# Main.net
KiCad netlist of a schematic drawn in Altium Designer
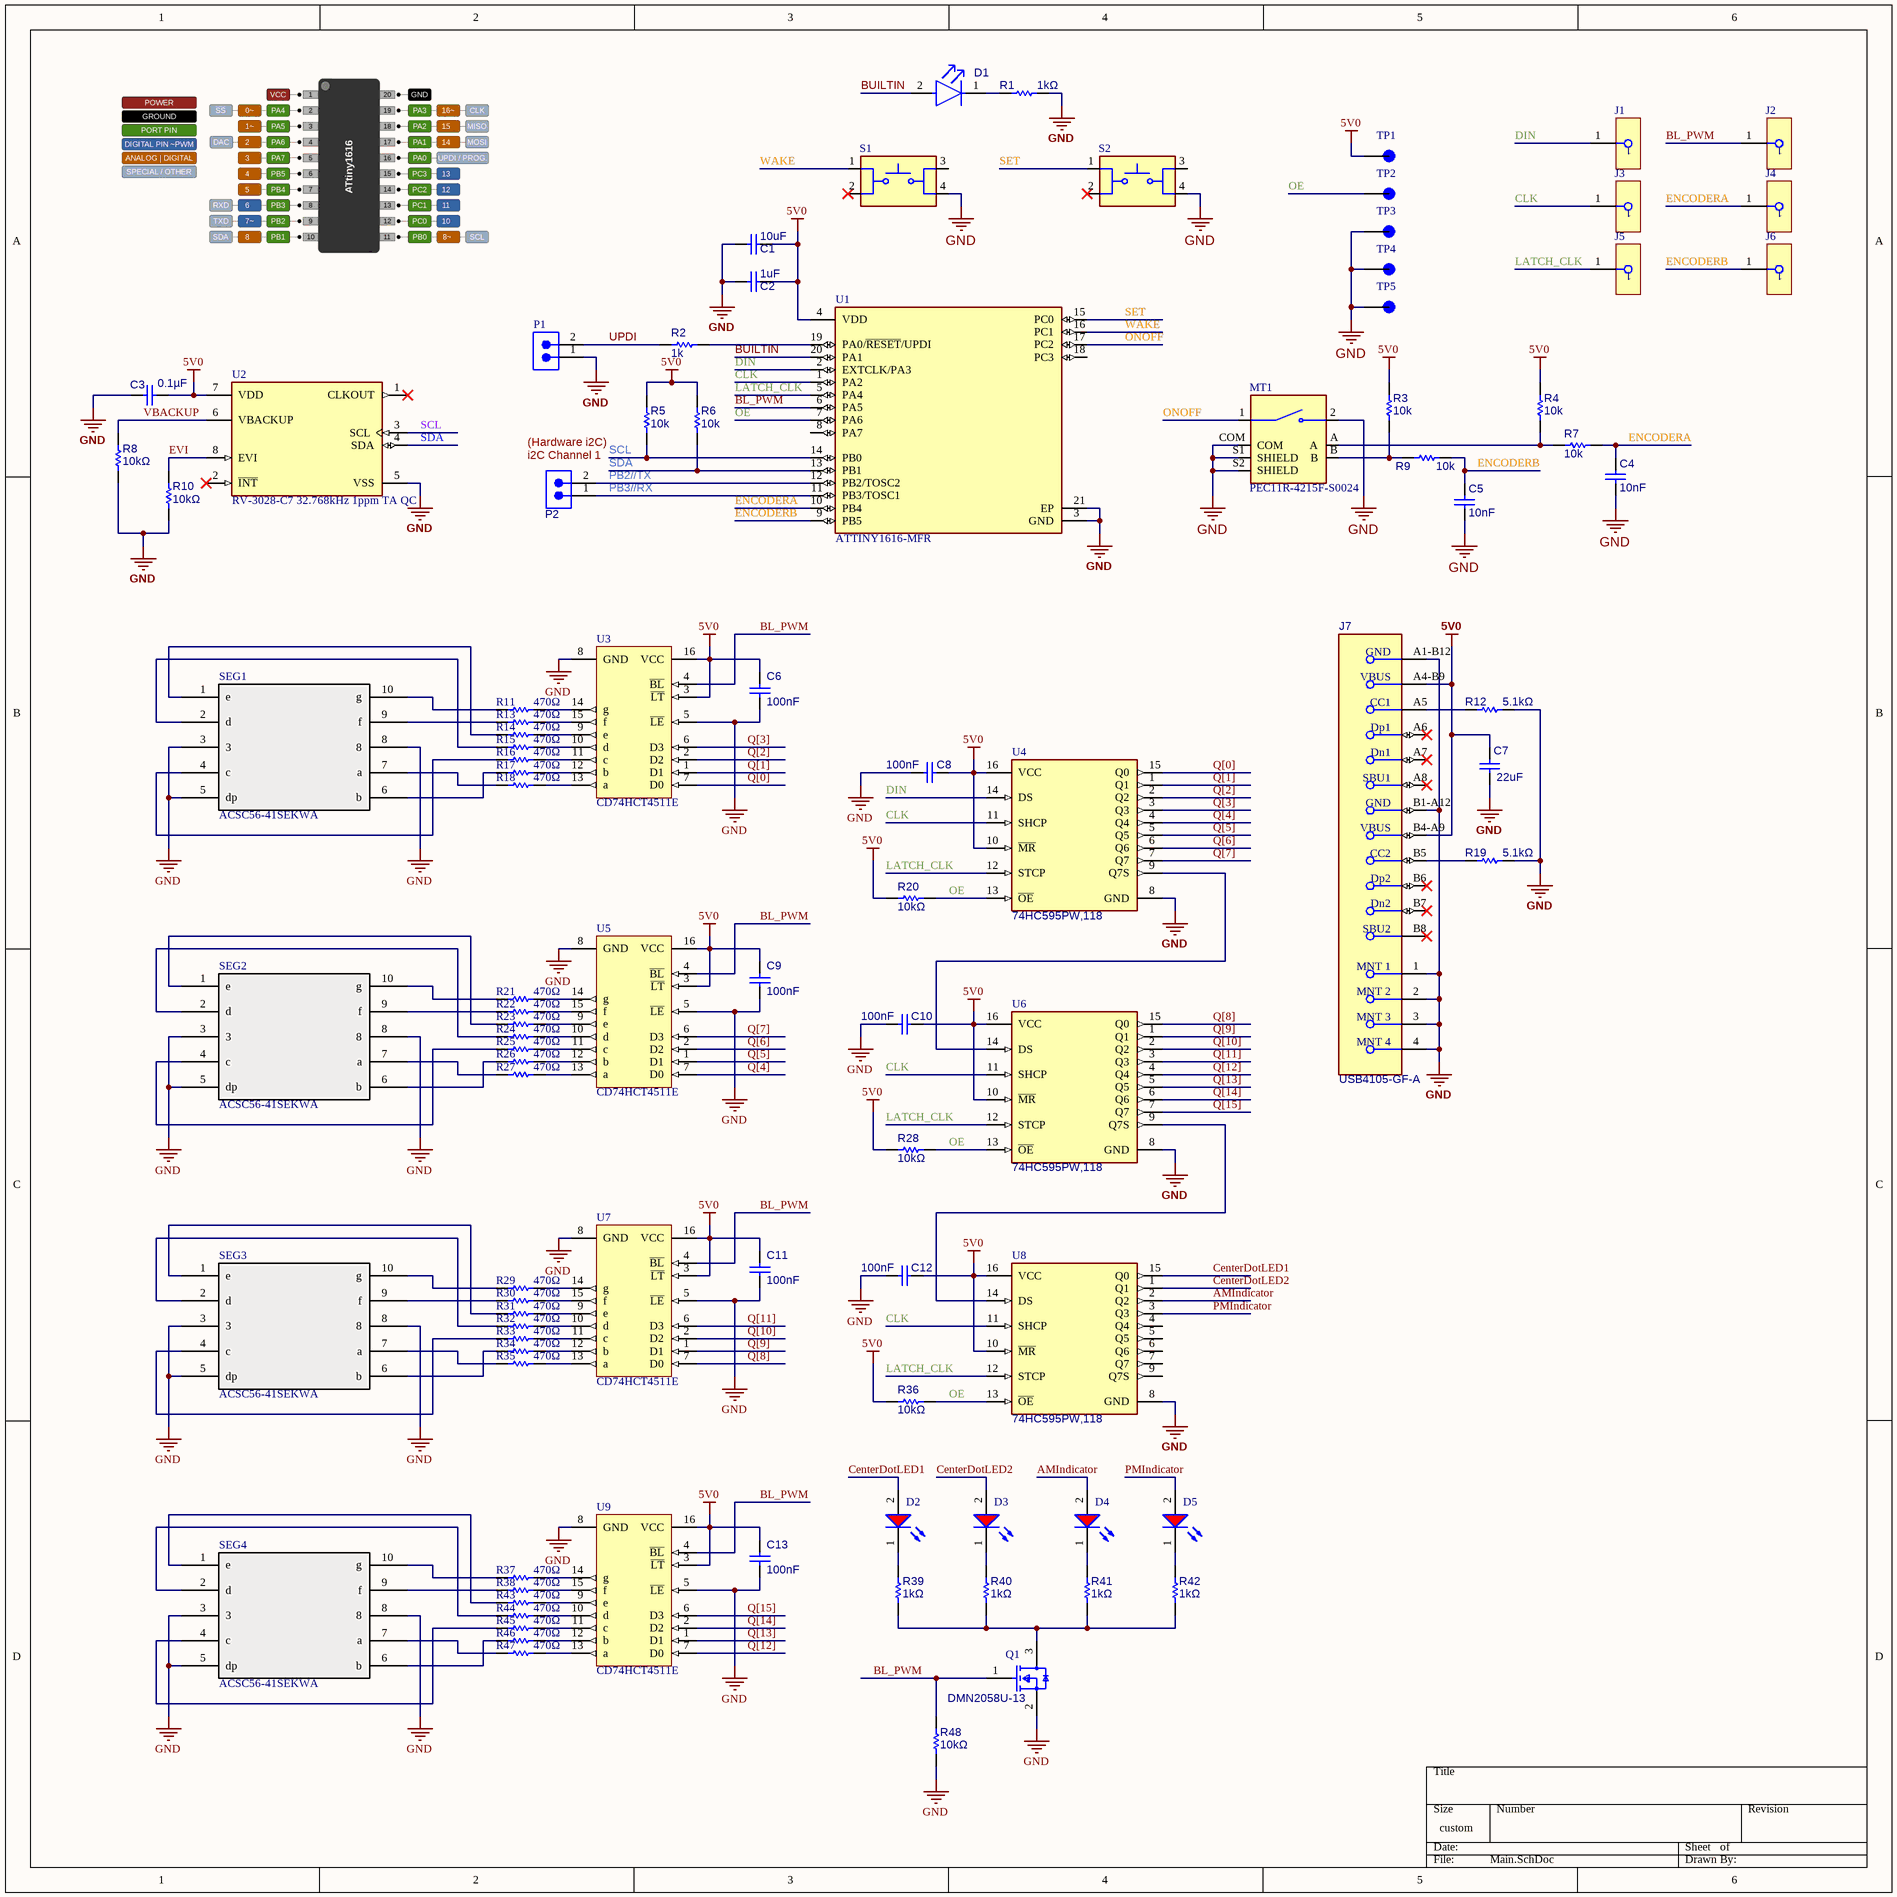
[diagram p0: Main.SchDoc]

(export (version "E")
  (design (tool "Eeschema 10.0.6"))
  (components
    (comp (ref "C1")
      (value "10uF")
      (footprint "WCAP-CSGP_0603_L1.6W0.8H0.8_Reflow")
      (description "10V tolerance")
      (libsource (lib "Altium Content Vault") (part "Capacitor_Non-Polarized"))
    )
    (comp (ref "C2")
      (value "1uF")
      (footprint "WCAP-CSGP_0603_L1.6W0.8H0.8_Reflow")
      (description "10V tolerance")
      (libsource (lib "Altium Content Vault") (part "Capacitor_Non-Polarized"))
    )
    (comp (ref "C3")
      (value "0.1µF")
      (footprint "WCAP-CSGP_0603_L1.6W0.8H0.8_Reflow")
      (description "10V tolerance")
      (libsource (lib "Altium Content Vault") (part "Capacitor_Non-Polarized"))
    )
    (comp (ref "C4")
      (value "10nF")
      (footprint "WCAP-CSGP_0603_L1.6W0.8H0.8_Reflow")
      (description "10V tolerance")
      (libsource (lib "Altium Content Vault") (part "Capacitor_Non-Polarized"))
    )
    (comp (ref "C5")
      (value "10nF")
      (footprint "WCAP-CSGP_0603_L1.6W0.8H0.8_Reflow")
      (description "10V tolerance")
      (libsource (lib "Altium Content Vault") (part "Capacitor_Non-Polarized"))
    )
    (comp (ref "C6")
      (value "100nF")
      (footprint "WCAP-CSGP_0603_L1.6W0.8H0.8_Reflow")
      (description "10V tolerance")
      (libsource (lib "Altium Content Vault") (part "Capacitor_Non-Polarized"))
    )
    (comp (ref "C7")
      (value "22uF")
      (footprint "WCAP-CSGP_0603_L1.6W0.8H0.8_Reflow")
      (description "10V tolerance")
      (libsource (lib "Altium Content Vault") (part "Capacitor_Non-Polarized"))
    )
    (comp (ref "C8")
      (value "100nF")
      (footprint "WCAP-CSGP_0603_L1.6W0.8H0.8_Reflow")
      (description "10V tolerance")
      (libsource (lib "Altium Content Vault") (part "Capacitor_Non-Polarized"))
    )
    (comp (ref "C9")
      (value "100nF")
      (footprint "WCAP-CSGP_0603_L1.6W0.8H0.8_Reflow")
      (description "10V tolerance")
      (libsource (lib "Altium Content Vault") (part "Capacitor_Non-Polarized"))
    )
    (comp (ref "C10")
      (value "100nF")
      (footprint "WCAP-CSGP_0603_L1.6W0.8H0.8_Reflow")
      (description "10V tolerance")
      (libsource (lib "Altium Content Vault") (part "Capacitor_Non-Polarized"))
    )
    (comp (ref "C11")
      (value "100nF")
      (footprint "WCAP-CSGP_0603_L1.6W0.8H0.8_Reflow")
      (description "10V tolerance")
      (libsource (lib "Altium Content Vault") (part "Capacitor_Non-Polarized"))
    )
    (comp (ref "C12")
      (value "100nF")
      (footprint "WCAP-CSGP_0603_L1.6W0.8H0.8_Reflow")
      (description "10V tolerance")
      (libsource (lib "Altium Content Vault") (part "Capacitor_Non-Polarized"))
    )
    (comp (ref "C13")
      (value "100nF")
      (footprint "WCAP-CSGP_0603_L1.6W0.8H0.8_Reflow")
      (description "10V tolerance")
      (libsource (lib "Altium Content Vault") (part "Capacitor_Non-Polarized"))
    )
    (comp (ref "D1")
      (value "LTST-C190KGKT")
      (footprint "FP-LTST-C190KGKT-MFG")
      (description "LED GREEN CLEAR CHIP SMD")
      (libsource (lib "Altium Content Vault") (part "8706943c75ba83719d021d2fdc84c58"))
    )
    (comp (ref "D2")
      (value "150120RS75000")
      (footprint "WL-SMCW_1206_150120xx75000")
      (description "WL-SMCW SMT Mono-Color Chip LED Waterclear")
      (libsource (lib "Altium Content Vault") (part "LED_Red_2A-1K"))
    )
    (comp (ref "D3")
      (value "150120RS75000")
      (footprint "WL-SMCW_1206_150120xx75000")
      (description "WL-SMCW SMT Mono-Color Chip LED Waterclear")
      (libsource (lib "Altium Content Vault") (part "LED_Red_2A-1K"))
    )
    (comp (ref "D4")
      (value "150120RS75000")
      (footprint "WL-SMCW_1206_150120xx75000")
      (description "WL-SMCW SMT Mono-Color Chip LED Waterclear")
      (libsource (lib "Altium Content Vault") (part "LED_Red_2A-1K"))
    )
    (comp (ref "D5")
      (value "150120RS75000")
      (footprint "WL-SMCW_1206_150120xx75000")
      (description "WL-SMCW SMT Mono-Color Chip LED Waterclear")
      (libsource (lib "Altium Content Vault") (part "LED_Red_2A-1K"))
    )
    (comp (ref "J1")
      (value "5019")
      (footprint "5019_MFG")
      (description "Phosphor Bronze Contact Miniature Silver Plated Surface Mount Test Points")
      (libsource (lib "Altium Content Vault") (part "2b5a64f1d553f7b761d27cd6d0c3a70"))
    )
    (comp (ref "J2")
      (value "5019")
      (footprint "5019_MFG")
      (description "Phosphor Bronze Contact Miniature Silver Plated Surface Mount Test Points")
      (libsource (lib "Altium Content Vault") (part "2b5a64f1d553f7b761d27cd6d0c3a70"))
    )
    (comp (ref "J3")
      (value "5019")
      (footprint "5019_MFG")
      (description "Phosphor Bronze Contact Miniature Silver Plated Surface Mount Test Points")
      (libsource (lib "Altium Content Vault") (part "2b5a64f1d553f7b761d27cd6d0c3a70"))
    )
    (comp (ref "J4")
      (value "5019")
      (footprint "5019_MFG")
      (description "Phosphor Bronze Contact Miniature Silver Plated Surface Mount Test Points")
      (libsource (lib "Altium Content Vault") (part "2b5a64f1d553f7b761d27cd6d0c3a70"))
    )
    (comp (ref "J5")
      (value "5019")
      (footprint "5019_MFG")
      (description "Phosphor Bronze Contact Miniature Silver Plated Surface Mount Test Points")
      (libsource (lib "Altium Content Vault") (part "2b5a64f1d553f7b761d27cd6d0c3a70"))
    )
    (comp (ref "J6")
      (value "5019")
      (footprint "5019_MFG")
      (description "Phosphor Bronze Contact Miniature Silver Plated Surface Mount Test Points")
      (libsource (lib "Altium Content Vault") (part "2b5a64f1d553f7b761d27cd6d0c3a70"))
    )
    (comp (ref "J7")
      (value "USB4105-GF-A")
      (footprint "FP-USB4105-GF-A-MFG")
      (description "CONN RCPT USB2.0 TYPEC 5A")
      (fields
        (field (name "MANUFACTURER") "GCT")
        (field (name "OCTOPART") "https://octopart.com/usb4105-gf-a-gct-106627878")
      )
      (libsource (lib "Altium Content Vault") (part "e7c17a616881a82b79941196b4bec10"))
    )
    (comp (ref "MT1")
      (value "PEC11R-4215F-S0024")
      (footprint "XDCR_PEC11R-4215F-S0024")
      (description "Incremental Encoder, 12 Mm, Contact Rating 10 Ma - 5 Vdc")
      (libsource (lib "PEC11R-4215F-S0024") (part "PEC11R-4215F-S0024"))
    )
    (comp (ref "P1")
      (value "61300211121")
      (footprint "61300211121")
      (description "THT Vertical Pin Header WR-PHD, Pitch 2.54 mm, Single Row, 2 pins")
      (libsource (lib "") (part "Header_Male_1R_02P_1"))
    )
    (comp (ref "P2")
      (value "61300211121")
      (footprint "61300211121")
      (libsource (lib "Altium Content Vault") (part "Header_Male_1R_02P"))
    )
    (comp (ref "Q1")
      (value "DMN2058U-13")
      (footprint "FP-C04-17458-MFG")
      (description "TN2130K1-G Mosfet, N-Channel Enhancement-Mode, 300V, 25 Ohm Rohs Compliant: Yes")
      (libsource (lib "Altium Content Vault") (part "3b9c635fedb024a5347a57b145af9cc"))
    )
    (comp (ref "R1")
      (value "1kΩ")
      (footprint "RESC1608X55X25NL10T15")
      (libsource (lib "Altium Content Vault") (part "RES"))
    )
    (comp (ref "R2")
      (value "1k")
      (footprint "RESC1608X55X25NL10T15")
      (libsource (lib "Altium Content Vault") (part "RES"))
    )
    (comp (ref "R3")
      (value "10k")
      (footprint "RESC1608X55X25NL10T15")
      (libsource (lib "Altium Content Vault") (part "RES"))
    )
    (comp (ref "R4")
      (value "10k")
      (footprint "RESC1608X55X25NL10T15")
      (libsource (lib "Altium Content Vault") (part "RES"))
    )
    (comp (ref "R5")
      (value "10k")
      (footprint "RESC1608X55X25NL10T15")
      (libsource (lib "Altium Content Vault") (part "RES"))
    )
    (comp (ref "R6")
      (value "10k")
      (footprint "RESC1608X55X25NL10T15")
      (libsource (lib "Altium Content Vault") (part "RES"))
    )
    (comp (ref "R7")
      (value "10k")
      (footprint "RESC1608X55X25NL10T15")
      (libsource (lib "Altium Content Vault") (part "RES"))
    )
    (comp (ref "R8")
      (value "10kΩ")
      (footprint "RESC1608X55X25NL10T15")
      (libsource (lib "Altium Content Vault") (part "RES"))
    )
    (comp (ref "R9")
      (value "10k")
      (footprint "RESC1608X55X25NL10T15")
      (libsource (lib "Altium Content Vault") (part "RES"))
    )
    (comp (ref "R10")
      (value "10kΩ")
      (footprint "RESC1608X55X25NL10T15")
      (libsource (lib "Altium Content Vault") (part "RES"))
    )
    (comp (ref "R11")
      (value "470Ω")
      (footprint "RESC3216X70X50NL05T20")
      (fields (field (name "PART NUMBER") "ERJ8ENF3300V") (field (name "MANUFACTURER") "Panasonic"))
      (libsource (lib "Altium Content Vault") (part "RES"))
    )
    (comp (ref "R12")
      (value "5.1kΩ")
      (footprint "RESC1608X55X25NL10T15")
      (libsource (lib "Altium Content Vault") (part "RES"))
    )
    (comp (ref "R13")
      (value "470Ω")
      (footprint "RESC3216X70X50NL05T20")
      (fields (field (name "PART NUMBER") "ERJ8ENF3300V") (field (name "MANUFACTURER") "Panasonic"))
      (libsource (lib "Altium Content Vault") (part "RES"))
    )
    (comp (ref "R14")
      (value "470Ω")
      (footprint "RESC3216X70X50NL05T20")
      (fields (field (name "PART NUMBER") "ERJ8ENF3300V") (field (name "MANUFACTURER") "Panasonic"))
      (libsource (lib "Altium Content Vault") (part "RES"))
    )
    (comp (ref "R15")
      (value "470Ω")
      (footprint "RESC3216X70X50NL05T20")
      (fields (field (name "PART NUMBER") "ERJ8ENF3300V") (field (name "MANUFACTURER") "Panasonic"))
      (libsource (lib "Altium Content Vault") (part "RES"))
    )
    (comp (ref "R16")
      (value "470Ω")
      (footprint "RESC3216X70X50NL05T20")
      (fields (field (name "PART NUMBER") "ERJ8ENF3300V") (field (name "MANUFACTURER") "Panasonic"))
      (libsource (lib "Altium Content Vault") (part "RES"))
    )
    (comp (ref "R17")
      (value "470Ω")
      (footprint "RESC3216X70X50NL05T20")
      (fields (field (name "PART NUMBER") "ERJ8ENF3300V") (field (name "MANUFACTURER") "Panasonic"))
      (libsource (lib "Altium Content Vault") (part "RES"))
    )
    (comp (ref "R18")
      (value "470Ω")
      (footprint "RESC3216X70X50NL05T20")
      (fields (field (name "PART NUMBER") "ERJ8ENF3300V") (field (name "MANUFACTURER") "Panasonic"))
      (libsource (lib "Altium Content Vault") (part "RES"))
    )
    (comp (ref "R19")
      (value "5.1kΩ")
      (footprint "RESC1608X55X25NL10T15")
      (libsource (lib "Altium Content Vault") (part "RES"))
    )
    (comp (ref "R20")
      (value "10kΩ")
      (footprint "RESC1608X55X25NL10T15")
      (libsource (lib "Altium Content Vault") (part "RES"))
    )
    (comp (ref "R21")
      (value "470Ω")
      (footprint "RESC3216X70X50NL05T20")
      (fields (field (name "PART NUMBER") "ERJ8ENF3300V") (field (name "MANUFACTURER") "Panasonic"))
      (libsource (lib "Altium Content Vault") (part "RES"))
    )
    (comp (ref "R22")
      (value "470Ω")
      (footprint "RESC3216X70X50NL05T20")
      (fields (field (name "PART NUMBER") "ERJ8ENF3300V") (field (name "MANUFACTURER") "Panasonic"))
      (libsource (lib "Altium Content Vault") (part "RES"))
    )
    (comp (ref "R23")
      (value "470Ω")
      (footprint "RESC3216X70X50NL05T20")
      (fields (field (name "PART NUMBER") "ERJ8ENF3300V") (field (name "MANUFACTURER") "Panasonic"))
      (libsource (lib "Altium Content Vault") (part "RES"))
    )
    (comp (ref "R24")
      (value "470Ω")
      (footprint "RESC3216X70X50NL05T20")
      (fields (field (name "PART NUMBER") "ERJ8ENF3300V") (field (name "MANUFACTURER") "Panasonic"))
      (libsource (lib "Altium Content Vault") (part "RES"))
    )
    (comp (ref "R25")
      (value "470Ω")
      (footprint "RESC3216X70X50NL05T20")
      (fields (field (name "PART NUMBER") "ERJ8ENF3300V") (field (name "MANUFACTURER") "Panasonic"))
      (libsource (lib "Altium Content Vault") (part "RES"))
    )
    (comp (ref "R26")
      (value "470Ω")
      (footprint "RESC3216X70X50NL05T20")
      (fields (field (name "PART NUMBER") "ERJ8ENF3300V") (field (name "MANUFACTURER") "Panasonic"))
      (libsource (lib "Altium Content Vault") (part "RES"))
    )
    (comp (ref "R27")
      (value "470Ω")
      (footprint "RESC3216X70X50NL05T20")
      (fields (field (name "PART NUMBER") "ERJ8ENF3300V") (field (name "MANUFACTURER") "Panasonic"))
      (libsource (lib "Altium Content Vault") (part "RES"))
    )
    (comp (ref "R28")
      (value "10kΩ")
      (footprint "RESC1608X55X25NL10T15")
      (libsource (lib "Altium Content Vault") (part "RES"))
    )
    (comp (ref "R29")
      (value "470Ω")
      (footprint "RESC3216X70X50NL05T20")
      (fields (field (name "PART NUMBER") "ERJ8ENF3300V") (field (name "MANUFACTURER") "Panasonic"))
      (libsource (lib "Altium Content Vault") (part "RES"))
    )
    (comp (ref "R30")
      (value "470Ω")
      (footprint "RESC3216X70X50NL05T20")
      (fields (field (name "PART NUMBER") "ERJ8ENF3300V") (field (name "MANUFACTURER") "Panasonic"))
      (libsource (lib "Altium Content Vault") (part "RES"))
    )
    (comp (ref "R31")
      (value "470Ω")
      (footprint "RESC3216X70X50NL05T20")
      (fields (field (name "PART NUMBER") "ERJ8ENF3300V") (field (name "MANUFACTURER") "Panasonic"))
      (libsource (lib "Altium Content Vault") (part "RES"))
    )
    (comp (ref "R32")
      (value "470Ω")
      (footprint "RESC3216X70X50NL05T20")
      (fields (field (name "PART NUMBER") "ERJ8ENF3300V") (field (name "MANUFACTURER") "Panasonic"))
      (libsource (lib "Altium Content Vault") (part "RES"))
    )
    (comp (ref "R33")
      (value "470Ω")
      (footprint "RESC3216X70X50NL05T20")
      (fields (field (name "PART NUMBER") "ERJ8ENF3300V") (field (name "MANUFACTURER") "Panasonic"))
      (libsource (lib "Altium Content Vault") (part "RES"))
    )
    (comp (ref "R34")
      (value "470Ω")
      (footprint "RESC3216X70X50NL05T20")
      (fields (field (name "PART NUMBER") "ERJ8ENF3300V") (field (name "MANUFACTURER") "Panasonic"))
      (libsource (lib "Altium Content Vault") (part "RES"))
    )
    (comp (ref "R35")
      (value "470Ω")
      (footprint "RESC3216X70X50NL05T20")
      (fields (field (name "PART NUMBER") "ERJ8ENF3300V") (field (name "MANUFACTURER") "Panasonic"))
      (libsource (lib "Altium Content Vault") (part "RES"))
    )
    (comp (ref "R36")
      (value "10kΩ")
      (footprint "RESC1608X55X25NL10T15")
      (libsource (lib "Altium Content Vault") (part "RES"))
    )
    (comp (ref "R37")
      (value "470Ω")
      (footprint "RESC3216X70X50NL05T20")
      (fields (field (name "PART NUMBER") "ERJ8ENF3300V") (field (name "MANUFACTURER") "Panasonic"))
      (libsource (lib "Altium Content Vault") (part "RES"))
    )
    (comp (ref "R38")
      (value "470Ω")
      (footprint "RESC3216X70X50NL05T20")
      (fields (field (name "PART NUMBER") "ERJ8ENF3300V") (field (name "MANUFACTURER") "Panasonic"))
      (libsource (lib "Altium Content Vault") (part "RES"))
    )
    (comp (ref "R39")
      (value "1kΩ")
      (footprint "RESC1608X55X25NL10T15")
      (libsource (lib "Altium Content Vault") (part "RES"))
    )
    (comp (ref "R40")
      (value "1kΩ")
      (footprint "RESC1608X55X25NL10T15")
      (libsource (lib "Altium Content Vault") (part "RES"))
    )
    (comp (ref "R41")
      (value "1kΩ")
      (footprint "RESC1608X55X25NL10T15")
      (libsource (lib "Altium Content Vault") (part "RES"))
    )
    (comp (ref "R42")
      (value "1kΩ")
      (footprint "RESC1608X55X25NL10T15")
      (libsource (lib "Altium Content Vault") (part "RES"))
    )
    (comp (ref "R43")
      (value "470Ω")
      (footprint "RESC3216X70X50NL05T20")
      (fields (field (name "PART NUMBER") "ERJ8ENF3300V") (field (name "MANUFACTURER") "Panasonic"))
      (libsource (lib "Altium Content Vault") (part "RES"))
    )
    (comp (ref "R44")
      (value "470Ω")
      (footprint "RESC3216X70X50NL05T20")
      (fields (field (name "PART NUMBER") "ERJ8ENF3300V") (field (name "MANUFACTURER") "Panasonic"))
      (libsource (lib "Altium Content Vault") (part "RES"))
    )
    (comp (ref "R45")
      (value "470Ω")
      (footprint "RESC3216X70X50NL05T20")
      (fields (field (name "PART NUMBER") "ERJ8ENF3300V") (field (name "MANUFACTURER") "Panasonic"))
      (libsource (lib "Altium Content Vault") (part "RES"))
    )
    (comp (ref "R46")
      (value "470Ω")
      (footprint "RESC3216X70X50NL05T20")
      (fields (field (name "PART NUMBER") "ERJ8ENF3300V") (field (name "MANUFACTURER") "Panasonic"))
      (libsource (lib "Altium Content Vault") (part "RES"))
    )
    (comp (ref "R47")
      (value "470Ω")
      (footprint "RESC3216X70X50NL05T20")
      (fields (field (name "PART NUMBER") "ERJ8ENF3300V") (field (name "MANUFACTURER") "Panasonic"))
      (libsource (lib "Altium Content Vault") (part "RES"))
    )
    (comp (ref "R48")
      (value "10kΩ")
      (footprint "RESC1608X55X25NL10T15")
      (libsource (lib "Altium Content Vault") (part "RES"))
    )
    (comp (ref "S1")
      (value "SWT0325-073016TSK_REVA")
      (footprint "SW_SWT0325-073016TSK_REVA")
      (description "6mm x 6mm Through Hole Tactile Switch")
      (fields (field (name "MF") "Global Connector Technology") (field (name "MP") "SWT0325-073016TSK"))
      (libsource (lib "SWT0325-073016TSK_REVA") (part "SWT0325-073016TSK_REVA"))
    )
    (comp (ref "S2")
      (value "SWT0325-073016TSK_REVA")
      (footprint "SW_SWT0325-073016TSK_REVA")
      (description "6mm x 6mm Through Hole Tactile Switch")
      (fields (field (name "MF") "Global Connector Technology") (field (name "MP") "SWT0325-073016TSK"))
      (libsource (lib "SWT0325-073016TSK_REVA") (part "SWT0325-073016TSK_REVA"))
    )
    (comp (ref "SEG1")
      (value "ACSC56-41SEKWA")
      (footprint "ACSC56-41SEKWA")
      (description "SMD 7-Segment Display")
      (libsource (lib "ACSC56-41SEKWA") (part "ACSC56-41SEKWA"))
    )
    (comp (ref "SEG2")
      (value "ACSC56-41SEKWA")
      (footprint "ACSC56-41SEKWA")
      (description "SMD 7-Segment Display")
      (libsource (lib "ACSC56-41SEKWA") (part "ACSC56-41SEKWA"))
    )
    (comp (ref "SEG3")
      (value "ACSC56-41SEKWA")
      (footprint "ACSC56-41SEKWA")
      (description "SMD 7-Segment Display")
      (libsource (lib "ACSC56-41SEKWA") (part "ACSC56-41SEKWA"))
    )
    (comp (ref "SEG4")
      (value "ACSC56-41SEKWA")
      (footprint "ACSC56-41SEKWA")
      (description "SMD 7-Segment Display")
      (libsource (lib "ACSC56-41SEKWA") (part "ACSC56-41SEKWA"))
    )
    (comp (ref "TP1")
      (value "1035")
      (footprint "KEYSTONE_1035")
      (description "Test Point PC Slotted THM Height .335 Brass/Tin ¦ Keystone Electronics 1035")
      (fields (field (name "MF") "Keystone Electronics"))
      (libsource (lib "1035") (part "1035"))
    )
    (comp (ref "TP2")
      (value "1035")
      (footprint "KEYSTONE_1035")
      (description "Test Point PC Slotted THM Height .335 Brass/Tin ¦ Keystone Electronics 1035")
      (fields (field (name "MF") "Keystone Electronics"))
      (libsource (lib "1035") (part "1035"))
    )
    (comp (ref "TP3")
      (value "1035")
      (footprint "KEYSTONE_1035")
      (description "Test Point PC Slotted THM Height .335 Brass/Tin ¦ Keystone Electronics 1035")
      (fields (field (name "MF") "Keystone Electronics"))
      (libsource (lib "1035") (part "1035"))
    )
    (comp (ref "TP4")
      (value "1035")
      (footprint "KEYSTONE_1035")
      (description "Test Point PC Slotted THM Height .335 Brass/Tin ¦ Keystone Electronics 1035")
      (fields (field (name "MF") "Keystone Electronics"))
      (libsource (lib "1035") (part "1035"))
    )
    (comp (ref "TP5")
      (value "1035")
      (footprint "KEYSTONE_1035")
      (description "Test Point PC Slotted THM Height .335 Brass/Tin ¦ Keystone Electronics 1035")
      (fields (field (name "MF") "Keystone Electronics"))
      (libsource (lib "1035") (part "1035"))
    )
    (comp (ref "U1")
      (value "ATTINY1616-MFR")
      (footprint "FP-C04-21380-MFG")
      (description "IC MCU 8BIT 16KB FLASH 20VQFN")
      (libsource (lib "Altium Content Vault") (part "b731dadd9c6de1c50dbd12acb163bbb"))
    )
    (comp (ref "U2")
      (value "RV-3028-C7 32.768kHz 1ppm TA QC")
      (footprint "FP-RV-3028-C7_32_768kHz_1-MFG")
      (description "Real Time Clock Serial 2byte Clock/Calendar/Alarm/Timer/Battery Backup 8-Pin CSMD T/R")
      (fields
        (field (name "OCTOPART") "https://octopart.com/rv-3028-c7+32.768khz+1ppm+ta+qc-micro+crystal-98880451")
        (field (name "MANUFACTURER") "Micro Crystal")
      )
      (libsource (lib "Altium Content Vault") (part "f06799675b941e5ee1fb77ef065374c"))
    )
    (comp (ref "U3")
      (value "CD74HCT4511E")
      (footprint "N0016A")
      (fields (field (name "MANUFACTURER") "Texas Instruments"))
      (libsource (lib "Altium Content Vault") (part "TI-CD54_74HCX4511-16"))
    )
    (comp (ref "U4")
      (value "74HC595PW,118")
      (footprint "FP-SOT403-1-MFG")
      (description "IC SHIFT REGISTER 8BIT 16TSSOP")
      (libsource (lib "Altium Content Vault") (part "27683e23285b137cd268a0f18c66bed"))
    )
    (comp (ref "U5")
      (value "CD74HCT4511E")
      (footprint "N0016A")
      (fields (field (name "MANUFACTURER") "Texas Instruments"))
      (libsource (lib "Altium Content Vault") (part "TI-CD54_74HCX4511-16"))
    )
    (comp (ref "U6")
      (value "74HC595PW,118")
      (footprint "FP-SOT403-1-MFG")
      (description "IC SHIFT REGISTER 8BIT 16TSSOP")
      (libsource (lib "Altium Content Vault") (part "27683e23285b137cd268a0f18c66bed"))
    )
    (comp (ref "U7")
      (value "CD74HCT4511E")
      (footprint "N0016A")
      (fields (field (name "MANUFACTURER") "Texas Instruments"))
      (libsource (lib "Altium Content Vault") (part "TI-CD54_74HCX4511-16"))
    )
    (comp (ref "U8")
      (value "74HC595PW,118")
      (footprint "FP-SOT403-1-MFG")
      (description "IC SHIFT REGISTER 8BIT 16TSSOP")
      (libsource (lib "Altium Content Vault") (part "27683e23285b137cd268a0f18c66bed"))
    )
    (comp (ref "U9")
      (value "CD74HCT4511E")
      (footprint "N0016A")
      (fields (field (name "MANUFACTURER") "Texas Instruments"))
      (libsource (lib "Altium Content Vault") (part "TI-CD54_74HCX4511-16"))
    )
  )
  (nets
    (net (code "1") (name "/AMIndicator") (class "Default")
      (node (ref "D4") (pin "2") (pinfunction "A_2") (pintype "passive"))
      (node (ref "U8") (pin "2") (pinfunction "Q2_2") (pintype "output"))
    )
    (net (code "2") (name "/BL_PWM") (class "Default")
      (node (ref "J2") (pin "1") (pinfunction "1_1") (pintype "passive"))
      (node (ref "Q1") (pin "1") (pinfunction "G_1") (pintype "passive"))
      (node (ref "R48") (pin "2") (pinfunction "2_2") (pintype "passive"))
      (node (ref "U1") (pin "6") (pinfunction "PA5_6") (pintype "bidirectional"))
      (node (ref "U3") (pin "4") (pinfunction "~{BL}_4") (pintype "input"))
      (node (ref "U5") (pin "4") (pinfunction "~{BL}_4") (pintype "input"))
      (node (ref "U7") (pin "4") (pinfunction "~{BL}_4") (pintype "input"))
      (node (ref "U9") (pin "4") (pinfunction "~{BL}_4") (pintype "input"))
    )
    (net (code "3") (name "/BUILTIN") (class "Default")
      (node (ref "D1") (pin "2") (pinfunction "A_2") (pintype "passive"))
      (node (ref "U1") (pin "20") (pinfunction "PA1_20") (pintype "bidirectional"))
    )
    (net (code "4") (name "/CLK") (class "Default")
      (node (ref "J3") (pin "1") (pinfunction "1_1") (pintype "passive"))
      (node (ref "U1") (pin "1") (pinfunction "PA2_1") (pintype "bidirectional"))
      (node (ref "U4") (pin "11") (pinfunction "SHCP_11") (pintype "input"))
      (node (ref "U6") (pin "11") (pinfunction "SHCP_11") (pintype "input"))
      (node (ref "U8") (pin "11") (pinfunction "SHCP_11") (pintype "input"))
    )
    (net (code "5") (name "/CenterDotLED1") (class "Default")
      (node (ref "D2") (pin "2") (pinfunction "A_2") (pintype "passive"))
      (node (ref "U8") (pin "15") (pinfunction "Q0_15") (pintype "output"))
    )
    (net (code "6") (name "/CenterDotLED2") (class "Default")
      (node (ref "D3") (pin "2") (pinfunction "A_2") (pintype "passive"))
      (node (ref "U8") (pin "1") (pinfunction "Q1_1") (pintype "output"))
    )
    (net (code "7") (name "/DIN") (class "Default")
      (node (ref "J1") (pin "1") (pinfunction "1_1") (pintype "passive"))
      (node (ref "U1") (pin "2") (pinfunction "EXTCLK/PA3_2") (pintype "bidirectional"))
      (node (ref "U4") (pin "14") (pinfunction "DS_14") (pintype "input"))
    )
    (net (code "8") (name "/ENCODERA") (class "Default")
      (node (ref "C4") (pin "1") (pinfunction "1_1") (pintype "passive"))
      (node (ref "J4") (pin "1") (pinfunction "1_1") (pintype "passive"))
      (node (ref "R7") (pin "2") (pinfunction "2_2") (pintype "passive"))
      (node (ref "U1") (pin "10") (pinfunction "PB4_10") (pintype "bidirectional"))
    )
    (net (code "9") (name "/ENCODERB") (class "Default")
      (node (ref "C5") (pin "1") (pinfunction "1_1") (pintype "passive"))
      (node (ref "J6") (pin "1") (pinfunction "1_1") (pintype "passive"))
      (node (ref "R9") (pin "2") (pinfunction "2_2") (pintype "passive"))
      (node (ref "U1") (pin "9") (pinfunction "PB5_9") (pintype "bidirectional"))
    )
    (net (code "10") (name "/EVI") (class "Default")
      (node (ref "R10") (pin "2") (pinfunction "2_2") (pintype "passive"))
      (node (ref "U2") (pin "8") (pinfunction "EVI_8") (pintype "input"))
    )
    (net (code "11") (name "/LATCH_CLK") (class "Default")
      (node (ref "J5") (pin "1") (pinfunction "1_1") (pintype "passive"))
      (node (ref "U1") (pin "5") (pinfunction "PA4_5") (pintype "bidirectional"))
      (node (ref "U4") (pin "12") (pinfunction "STCP_12") (pintype "input"))
      (node (ref "U6") (pin "12") (pinfunction "STCP_12") (pintype "input"))
      (node (ref "U8") (pin "12") (pinfunction "STCP_12") (pintype "input"))
    )
    (net (code "12") (name "/OE") (class "Default")
      (node (ref "R20") (pin "2") (pinfunction "2_2") (pintype "passive"))
      (node (ref "R28") (pin "2") (pinfunction "2_2") (pintype "passive"))
      (node (ref "R36") (pin "2") (pinfunction "2_2") (pintype "passive"))
      (node (ref "TP2") (pin "TP") (pinfunction "TP_TP") (pintype "passive"))
      (node (ref "U1") (pin "7") (pinfunction "PA6_7") (pintype "bidirectional"))
      (node (ref "U4") (pin "13") (pinfunction "~{OE}_13") (pintype "input"))
      (node (ref "U6") (pin "13") (pinfunction "~{OE}_13") (pintype "input"))
      (node (ref "U8") (pin "13") (pinfunction "~{OE}_13") (pintype "input"))
    )
    (net (code "13") (name "/ONOFF") (class "Default")
      (node (ref "MT1") (pin "1") (pinfunction "1_1") (pintype "passive"))
      (node (ref "U1") (pin "17") (pinfunction "PC2_17") (pintype "bidirectional"))
    )
    (net (code "14") (name "/PB2{slash}{slash}TX") (class "Default")
      (node (ref "P2") (pin "2") (pinfunction "2_2") (pintype "passive"))
      (node (ref "U1") (pin "12") (pinfunction "PB2/TOSC2_12") (pintype "bidirectional"))
    )
    (net (code "15") (name "/PB3{slash}{slash}RX") (class "Default")
      (node (ref "P2") (pin "1") (pinfunction "1_1") (pintype "passive"))
      (node (ref "U1") (pin "11") (pinfunction "PB3/TOSC1_11") (pintype "bidirectional"))
    )
    (net (code "16") (name "/PMIndicator") (class "Default")
      (node (ref "D5") (pin "2") (pinfunction "A_2") (pintype "passive"))
      (node (ref "U8") (pin "3") (pinfunction "Q3_3") (pintype "output"))
    )
    (net (code "17") (name "/Q[0]") (class "Default")
      (node (ref "U3") (pin "7") (pinfunction "D0_7") (pintype "input"))
      (node (ref "U4") (pin "15") (pinfunction "Q0_15") (pintype "output"))
    )
    (net (code "18") (name "/Q[1]") (class "Default")
      (node (ref "U3") (pin "1") (pinfunction "D1_1") (pintype "input"))
      (node (ref "U4") (pin "1") (pinfunction "Q1_1") (pintype "output"))
    )
    (net (code "19") (name "/Q[2]") (class "Default")
      (node (ref "U3") (pin "2") (pinfunction "D2_2") (pintype "input"))
      (node (ref "U4") (pin "2") (pinfunction "Q2_2") (pintype "output"))
    )
    (net (code "20") (name "/Q[3]") (class "Default")
      (node (ref "U3") (pin "6") (pinfunction "D3_6") (pintype "input"))
      (node (ref "U4") (pin "3") (pinfunction "Q3_3") (pintype "output"))
    )
    (net (code "21") (name "/Q[4]") (class "Default")
      (node (ref "U4") (pin "4") (pinfunction "Q4_4") (pintype "output"))
      (node (ref "U5") (pin "7") (pinfunction "D0_7") (pintype "input"))
    )
    (net (code "22") (name "/Q[5]") (class "Default")
      (node (ref "U4") (pin "5") (pinfunction "Q5_5") (pintype "output"))
      (node (ref "U5") (pin "1") (pinfunction "D1_1") (pintype "input"))
    )
    (net (code "23") (name "/Q[6]") (class "Default")
      (node (ref "U4") (pin "6") (pinfunction "Q6_6") (pintype "output"))
      (node (ref "U5") (pin "2") (pinfunction "D2_2") (pintype "input"))
    )
    (net (code "24") (name "/Q[7]") (class "Default")
      (node (ref "U4") (pin "7") (pinfunction "Q7_7") (pintype "output"))
      (node (ref "U5") (pin "6") (pinfunction "D3_6") (pintype "input"))
    )
    (net (code "25") (name "/Q[8]") (class "Default")
      (node (ref "U6") (pin "15") (pinfunction "Q0_15") (pintype "output"))
      (node (ref "U7") (pin "7") (pinfunction "D0_7") (pintype "input"))
    )
    (net (code "26") (name "/Q[9]") (class "Default")
      (node (ref "U6") (pin "1") (pinfunction "Q1_1") (pintype "output"))
      (node (ref "U7") (pin "1") (pinfunction "D1_1") (pintype "input"))
    )
    (net (code "27") (name "/Q[10]") (class "Default")
      (node (ref "U6") (pin "2") (pinfunction "Q2_2") (pintype "output"))
      (node (ref "U7") (pin "2") (pinfunction "D2_2") (pintype "input"))
    )
    (net (code "28") (name "/Q[11]") (class "Default")
      (node (ref "U6") (pin "3") (pinfunction "Q3_3") (pintype "output"))
      (node (ref "U7") (pin "6") (pinfunction "D3_6") (pintype "input"))
    )
    (net (code "29") (name "/Q[12]") (class "Default")
      (node (ref "U6") (pin "4") (pinfunction "Q4_4") (pintype "output"))
      (node (ref "U9") (pin "7") (pinfunction "D0_7") (pintype "input"))
    )
    (net (code "30") (name "/Q[13]") (class "Default")
      (node (ref "U6") (pin "5") (pinfunction "Q5_5") (pintype "output"))
      (node (ref "U9") (pin "1") (pinfunction "D1_1") (pintype "input"))
    )
    (net (code "31") (name "/Q[14]") (class "Default")
      (node (ref "U6") (pin "6") (pinfunction "Q6_6") (pintype "output"))
      (node (ref "U9") (pin "2") (pinfunction "D2_2") (pintype "input"))
    )
    (net (code "32") (name "/Q[15]") (class "Default")
      (node (ref "U6") (pin "7") (pinfunction "Q7_7") (pintype "output"))
      (node (ref "U9") (pin "6") (pinfunction "D3_6") (pintype "input"))
    )
    (net (code "33") (name "/SCL") (class "Default")
      (node (ref "R5") (pin "1") (pinfunction "1_1") (pintype "passive"))
      (node (ref "U1") (pin "14") (pinfunction "PB0_14") (pintype "bidirectional"))
      (node (ref "U2") (pin "3") (pinfunction "SCL_3") (pintype "input"))
    )
    (net (code "34") (name "/SDA") (class "Default")
      (node (ref "R6") (pin "1") (pinfunction "1_1") (pintype "passive"))
      (node (ref "U1") (pin "13") (pinfunction "PB1_13") (pintype "bidirectional"))
      (node (ref "U2") (pin "4") (pinfunction "SDA_4") (pintype "bidirectional"))
    )
    (net (code "35") (name "/SET") (class "Default")
      (node (ref "S2") (pin "1") (pinfunction "1_1") (pintype "passive"))
      (node (ref "U1") (pin "15") (pinfunction "PC0_15") (pintype "bidirectional"))
    )
    (net (code "36") (name "/UPDI") (class "Default")
      (node (ref "P1") (pin "2") (pinfunction "2_2") (pintype "passive"))
      (node (ref "R2") (pin "1") (pinfunction "1_1") (pintype "passive"))
    )
    (net (code "37") (name "/VBACKUP") (class "Default")
      (node (ref "R8") (pin "2") (pinfunction "2_2") (pintype "passive"))
      (node (ref "U2") (pin "6") (pinfunction "VBACKUP_6") (pintype "power_in"))
    )
    (net (code "38") (name "/WAKE") (class "Default")
      (node (ref "S1") (pin "1") (pinfunction "1_1") (pintype "passive"))
      (node (ref "U1") (pin "16") (pinfunction "PC1_16") (pintype "bidirectional"))
    )
    (net (code "39") (name "5V0") (class "Default")
      (node (ref "C1") (pin "2") (pinfunction "2_2") (pintype "passive"))
      (node (ref "C10") (pin "2") (pinfunction "2_2") (pintype "passive"))
      (node (ref "C11") (pin "2") (pinfunction "2_2") (pintype "passive"))
      (node (ref "C12") (pin "2") (pinfunction "2_2") (pintype "passive"))
      (node (ref "C13") (pin "2") (pinfunction "2_2") (pintype "passive"))
      (node (ref "C2") (pin "2") (pinfunction "2_2") (pintype "passive"))
      (node (ref "C3") (pin "1") (pinfunction "1_1") (pintype "passive"))
      (node (ref "C6") (pin "2") (pinfunction "2_2") (pintype "passive"))
      (node (ref "C7") (pin "2") (pinfunction "2_2") (pintype "passive"))
      (node (ref "C8") (pin "2") (pinfunction "2_2") (pintype "passive"))
      (node (ref "C9") (pin "2") (pinfunction "2_2") (pintype "passive"))
      (node (ref "J7") (pin "A4-B9") (pinfunction "VBUS_A4-B9") (pintype "power_in"))
      (node (ref "J7") (pin "B4-A9") (pinfunction "VBUS_B4-A9") (pintype "bidirectional"))
      (node (ref "R20") (pin "1") (pinfunction "1_1") (pintype "passive"))
      (node (ref "R28") (pin "1") (pinfunction "1_1") (pintype "passive"))
      (node (ref "R3") (pin "2") (pinfunction "2_2") (pintype "passive"))
      (node (ref "R36") (pin "1") (pinfunction "1_1") (pintype "passive"))
      (node (ref "R4") (pin "2") (pinfunction "2_2") (pintype "passive"))
      (node (ref "R5") (pin "2") (pinfunction "2_2") (pintype "passive"))
      (node (ref "R6") (pin "2") (pinfunction "2_2") (pintype "passive"))
      (node (ref "TP1") (pin "TP") (pinfunction "TP_TP") (pintype "passive"))
      (node (ref "U1") (pin "4") (pinfunction "VDD_4") (pintype "power_in"))
      (node (ref "U2") (pin "7") (pinfunction "VDD_7") (pintype "power_in"))
      (node (ref "U3") (pin "16") (pinfunction "VCC_16") (pintype "power_in"))
      (node (ref "U3") (pin "3") (pinfunction "~{LT}_3") (pintype "input"))
      (node (ref "U4") (pin "10") (pinfunction "~{MR}_10") (pintype "input"))
      (node (ref "U4") (pin "16") (pinfunction "VCC_16") (pintype "power_in"))
      (node (ref "U5") (pin "16") (pinfunction "VCC_16") (pintype "power_in"))
      (node (ref "U5") (pin "3") (pinfunction "~{LT}_3") (pintype "input"))
      (node (ref "U6") (pin "10") (pinfunction "~{MR}_10") (pintype "input"))
      (node (ref "U6") (pin "16") (pinfunction "VCC_16") (pintype "power_in"))
      (node (ref "U7") (pin "16") (pinfunction "VCC_16") (pintype "power_in"))
      (node (ref "U7") (pin "3") (pinfunction "~{LT}_3") (pintype "input"))
      (node (ref "U8") (pin "10") (pinfunction "~{MR}_10") (pintype "input"))
      (node (ref "U8") (pin "16") (pinfunction "VCC_16") (pintype "power_in"))
      (node (ref "U9") (pin "16") (pinfunction "VCC_16") (pintype "power_in"))
      (node (ref "U9") (pin "3") (pinfunction "~{LT}_3") (pintype "input"))
    )
    (net (code "40") (name "GND") (class "Default")
      (node (ref "C1") (pin "1") (pinfunction "1_1") (pintype "passive"))
      (node (ref "C10") (pin "1") (pinfunction "1_1") (pintype "passive"))
      (node (ref "C11") (pin "1") (pinfunction "1_1") (pintype "passive"))
      (node (ref "C12") (pin "1") (pinfunction "1_1") (pintype "passive"))
      (node (ref "C13") (pin "1") (pinfunction "1_1") (pintype "passive"))
      (node (ref "C2") (pin "1") (pinfunction "1_1") (pintype "passive"))
      (node (ref "C3") (pin "2") (pinfunction "2_2") (pintype "passive"))
      (node (ref "C4") (pin "2") (pinfunction "2_2") (pintype "passive"))
      (node (ref "C5") (pin "2") (pinfunction "2_2") (pintype "passive"))
      (node (ref "C6") (pin "1") (pinfunction "1_1") (pintype "passive"))
      (node (ref "C7") (pin "1") (pinfunction "1_1") (pintype "passive"))
      (node (ref "C8") (pin "1") (pinfunction "1_1") (pintype "passive"))
      (node (ref "C9") (pin "1") (pinfunction "1_1") (pintype "passive"))
      (node (ref "J7") (pin "1") (pinfunction "MNT_1_1") (pintype "power_in"))
      (node (ref "J7") (pin "2") (pinfunction "MNT_2_2") (pintype "power_in"))
      (node (ref "J7") (pin "3") (pinfunction "MNT_3_3") (pintype "power_in"))
      (node (ref "J7") (pin "4") (pinfunction "MNT_4_4") (pintype "power_in"))
      (node (ref "J7") (pin "A1-B12") (pinfunction "GND_A1-B12") (pintype "power_in"))
      (node (ref "J7") (pin "B1-A12") (pinfunction "GND_B1-A12") (pintype "bidirectional"))
      (node (ref "MT1") (pin "2") (pinfunction "2_2") (pintype "passive"))
      (node (ref "MT1") (pin "COM") (pinfunction "COM_COM") (pintype "passive"))
      (node (ref "MT1") (pin "S1") (pinfunction "SHIELD_S1") (pintype "passive"))
      (node (ref "MT1") (pin "S2") (pinfunction "SHIELD_S2") (pintype "passive"))
      (node (ref "P1") (pin "1") (pinfunction "1_1") (pintype "passive"))
      (node (ref "Q1") (pin "2") (pinfunction "S_2") (pintype "passive"))
      (node (ref "R1") (pin "1") (pinfunction "1_1") (pintype "passive"))
      (node (ref "R10") (pin "1") (pinfunction "1_1") (pintype "passive"))
      (node (ref "R12") (pin "1") (pinfunction "1_1") (pintype "passive"))
      (node (ref "R19") (pin "1") (pinfunction "1_1") (pintype "passive"))
      (node (ref "R48") (pin "1") (pinfunction "1_1") (pintype "passive"))
      (node (ref "R8") (pin "1") (pinfunction "1_1") (pintype "passive"))
      (node (ref "S1") (pin "4") (pinfunction "4_4") (pintype "passive"))
      (node (ref "S2") (pin "4") (pinfunction "4_4") (pintype "passive"))
      (node (ref "SEG1") (pin "3") (pinfunction "3_3") (pintype "passive"))
      (node (ref "SEG1") (pin "5") (pinfunction "dp_5") (pintype "passive"))
      (node (ref "SEG1") (pin "8") (pinfunction "8_8") (pintype "passive"))
      (node (ref "SEG2") (pin "3") (pinfunction "3_3") (pintype "passive"))
      (node (ref "SEG2") (pin "5") (pinfunction "dp_5") (pintype "passive"))
      (node (ref "SEG2") (pin "8") (pinfunction "8_8") (pintype "passive"))
      (node (ref "SEG3") (pin "3") (pinfunction "3_3") (pintype "passive"))
      (node (ref "SEG3") (pin "5") (pinfunction "dp_5") (pintype "passive"))
      (node (ref "SEG3") (pin "8") (pinfunction "8_8") (pintype "passive"))
      (node (ref "SEG4") (pin "3") (pinfunction "3_3") (pintype "passive"))
      (node (ref "SEG4") (pin "5") (pinfunction "dp_5") (pintype "passive"))
      (node (ref "SEG4") (pin "8") (pinfunction "8_8") (pintype "passive"))
      (node (ref "TP3") (pin "TP") (pinfunction "TP_TP") (pintype "passive"))
      (node (ref "TP4") (pin "TP") (pinfunction "TP_TP") (pintype "passive"))
      (node (ref "TP5") (pin "TP") (pinfunction "TP_TP") (pintype "passive"))
      (node (ref "U1") (pin "21") (pinfunction "EP_21") (pintype "power_in"))
      (node (ref "U1") (pin "3") (pinfunction "GND_3") (pintype "power_in"))
      (node (ref "U2") (pin "5") (pinfunction "VSS_5") (pintype "power_in"))
      (node (ref "U3") (pin "5") (pinfunction "~{LE}_5") (pintype "input"))
      (node (ref "U3") (pin "8") (pinfunction "GND_8") (pintype "power_in"))
      (node (ref "U4") (pin "8") (pinfunction "GND_8") (pintype "power_in"))
      (node (ref "U5") (pin "5") (pinfunction "~{LE}_5") (pintype "input"))
      (node (ref "U5") (pin "8") (pinfunction "GND_8") (pintype "power_in"))
      (node (ref "U6") (pin "8") (pinfunction "GND_8") (pintype "power_in"))
      (node (ref "U7") (pin "5") (pinfunction "~{LE}_5") (pintype "input"))
      (node (ref "U7") (pin "8") (pinfunction "GND_8") (pintype "power_in"))
      (node (ref "U8") (pin "8") (pinfunction "GND_8") (pintype "power_in"))
      (node (ref "U9") (pin "5") (pinfunction "~{LE}_5") (pintype "input"))
      (node (ref "U9") (pin "8") (pinfunction "GND_8") (pintype "power_in"))
    )
    (net (code "41") (name "Net-(D1-C)") (class "Default")
      (node (ref "D1") (pin "1") (pinfunction "C_1") (pintype "passive"))
      (node (ref "R1") (pin "2") (pinfunction "2_2") (pintype "passive"))
    )
    (net (code "42") (name "Net-(D2-K)") (class "Default")
      (node (ref "D2") (pin "1") (pinfunction "K_1") (pintype "passive"))
      (node (ref "R39") (pin "2") (pinfunction "2_2") (pintype "passive"))
    )
    (net (code "43") (name "Net-(D3-K)") (class "Default")
      (node (ref "D3") (pin "1") (pinfunction "K_1") (pintype "passive"))
      (node (ref "R40") (pin "2") (pinfunction "2_2") (pintype "passive"))
    )
    (net (code "44") (name "Net-(D4-K)") (class "Default")
      (node (ref "D4") (pin "1") (pinfunction "K_1") (pintype "passive"))
      (node (ref "R41") (pin "2") (pinfunction "2_2") (pintype "passive"))
    )
    (net (code "45") (name "Net-(D5-K)") (class "Default")
      (node (ref "D5") (pin "1") (pinfunction "K_1") (pintype "passive"))
      (node (ref "R42") (pin "2") (pinfunction "2_2") (pintype "passive"))
    )
    (net (code "46") (name "Net-(J7-CC1)") (class "Default")
      (node (ref "J7") (pin "A5") (pinfunction "CC1_A5") (pintype "power_in"))
      (node (ref "R12") (pin "2") (pinfunction "2_2") (pintype "passive"))
    )
    (net (code "47") (name "Net-(J7-CC2)") (class "Default")
      (node (ref "J7") (pin "B5") (pinfunction "CC2_B5") (pintype "bidirectional"))
      (node (ref "R19") (pin "2") (pinfunction "2_2") (pintype "passive"))
    )
    (net (code "48") (name "Net-(MT1-PadA)") (class "Default")
      (node (ref "MT1") (pin "A") (pinfunction "A_A") (pintype "passive"))
      (node (ref "R4") (pin "1") (pinfunction "1_1") (pintype "passive"))
      (node (ref "R7") (pin "1") (pinfunction "1_1") (pintype "passive"))
    )
    (net (code "49") (name "Net-(MT1-PadB)") (class "Default")
      (node (ref "MT1") (pin "B") (pinfunction "B_B") (pintype "passive"))
      (node (ref "R3") (pin "1") (pinfunction "1_1") (pintype "passive"))
      (node (ref "R9") (pin "1") (pinfunction "1_1") (pintype "passive"))
    )
    (net (code "50") (name "Net-(Q1-D)") (class "Default")
      (node (ref "Q1") (pin "3") (pinfunction "D_3") (pintype "passive"))
      (node (ref "R39") (pin "1") (pinfunction "1_1") (pintype "passive"))
      (node (ref "R40") (pin "1") (pinfunction "1_1") (pintype "passive"))
      (node (ref "R41") (pin "1") (pinfunction "1_1") (pintype "passive"))
      (node (ref "R42") (pin "1") (pinfunction "1_1") (pintype "passive"))
    )
    (net (code "51") (name "Net-(SEG1-a)") (class "Default")
      (node (ref "R18") (pin "1") (pinfunction "1_1") (pintype "passive"))
      (node (ref "SEG1") (pin "7") (pinfunction "a_7") (pintype "passive"))
    )
    (net (code "52") (name "Net-(SEG1-b)") (class "Default")
      (node (ref "R17") (pin "1") (pinfunction "1_1") (pintype "passive"))
      (node (ref "SEG1") (pin "6") (pinfunction "b_6") (pintype "passive"))
    )
    (net (code "53") (name "Net-(SEG1-c)") (class "Default")
      (node (ref "R16") (pin "1") (pinfunction "1_1") (pintype "passive"))
      (node (ref "SEG1") (pin "4") (pinfunction "c_4") (pintype "passive"))
    )
    (net (code "54") (name "Net-(SEG1-d)") (class "Default")
      (node (ref "R15") (pin "1") (pinfunction "1_1") (pintype "passive"))
      (node (ref "SEG1") (pin "2") (pinfunction "d_2") (pintype "passive"))
    )
    (net (code "55") (name "Net-(SEG1-e)") (class "Default")
      (node (ref "R14") (pin "1") (pinfunction "1_1") (pintype "passive"))
      (node (ref "SEG1") (pin "1") (pinfunction "e_1") (pintype "passive"))
    )
    (net (code "56") (name "Net-(SEG1-f)") (class "Default")
      (node (ref "R13") (pin "1") (pinfunction "1_1") (pintype "passive"))
      (node (ref "SEG1") (pin "9") (pinfunction "f_9") (pintype "passive"))
    )
    (net (code "57") (name "Net-(SEG1-g)") (class "Default")
      (node (ref "R11") (pin "1") (pinfunction "1_1") (pintype "passive"))
      (node (ref "SEG1") (pin "10") (pinfunction "g_10") (pintype "passive"))
    )
    (net (code "58") (name "Net-(SEG2-a)") (class "Default")
      (node (ref "R27") (pin "1") (pinfunction "1_1") (pintype "passive"))
      (node (ref "SEG2") (pin "7") (pinfunction "a_7") (pintype "passive"))
    )
    (net (code "59") (name "Net-(SEG2-b)") (class "Default")
      (node (ref "R26") (pin "1") (pinfunction "1_1") (pintype "passive"))
      (node (ref "SEG2") (pin "6") (pinfunction "b_6") (pintype "passive"))
    )
    (net (code "60") (name "Net-(SEG2-c)") (class "Default")
      (node (ref "R25") (pin "1") (pinfunction "1_1") (pintype "passive"))
      (node (ref "SEG2") (pin "4") (pinfunction "c_4") (pintype "passive"))
    )
    (net (code "61") (name "Net-(SEG2-d)") (class "Default")
      (node (ref "R24") (pin "1") (pinfunction "1_1") (pintype "passive"))
      (node (ref "SEG2") (pin "2") (pinfunction "d_2") (pintype "passive"))
    )
    (net (code "62") (name "Net-(SEG2-e)") (class "Default")
      (node (ref "R23") (pin "1") (pinfunction "1_1") (pintype "passive"))
      (node (ref "SEG2") (pin "1") (pinfunction "e_1") (pintype "passive"))
    )
    (net (code "63") (name "Net-(SEG2-f)") (class "Default")
      (node (ref "R22") (pin "1") (pinfunction "1_1") (pintype "passive"))
      (node (ref "SEG2") (pin "9") (pinfunction "f_9") (pintype "passive"))
    )
    (net (code "64") (name "Net-(SEG2-g)") (class "Default")
      (node (ref "R21") (pin "1") (pinfunction "1_1") (pintype "passive"))
      (node (ref "SEG2") (pin "10") (pinfunction "g_10") (pintype "passive"))
    )
    (net (code "65") (name "Net-(SEG3-a)") (class "Default")
      (node (ref "R35") (pin "1") (pinfunction "1_1") (pintype "passive"))
      (node (ref "SEG3") (pin "7") (pinfunction "a_7") (pintype "passive"))
    )
    (net (code "66") (name "Net-(SEG3-b)") (class "Default")
      (node (ref "R34") (pin "1") (pinfunction "1_1") (pintype "passive"))
      (node (ref "SEG3") (pin "6") (pinfunction "b_6") (pintype "passive"))
    )
    (net (code "67") (name "Net-(SEG3-c)") (class "Default")
      (node (ref "R33") (pin "1") (pinfunction "1_1") (pintype "passive"))
      (node (ref "SEG3") (pin "4") (pinfunction "c_4") (pintype "passive"))
    )
    (net (code "68") (name "Net-(SEG3-d)") (class "Default")
      (node (ref "R32") (pin "1") (pinfunction "1_1") (pintype "passive"))
      (node (ref "SEG3") (pin "2") (pinfunction "d_2") (pintype "passive"))
    )
    (net (code "69") (name "Net-(SEG3-e)") (class "Default")
      (node (ref "R31") (pin "1") (pinfunction "1_1") (pintype "passive"))
      (node (ref "SEG3") (pin "1") (pinfunction "e_1") (pintype "passive"))
    )
    (net (code "70") (name "Net-(SEG3-f)") (class "Default")
      (node (ref "R30") (pin "1") (pinfunction "1_1") (pintype "passive"))
      (node (ref "SEG3") (pin "9") (pinfunction "f_9") (pintype "passive"))
    )
    (net (code "71") (name "Net-(SEG3-g)") (class "Default")
      (node (ref "R29") (pin "1") (pinfunction "1_1") (pintype "passive"))
      (node (ref "SEG3") (pin "10") (pinfunction "g_10") (pintype "passive"))
    )
    (net (code "72") (name "Net-(SEG4-a)") (class "Default")
      (node (ref "R47") (pin "1") (pinfunction "1_1") (pintype "passive"))
      (node (ref "SEG4") (pin "7") (pinfunction "a_7") (pintype "passive"))
    )
    (net (code "73") (name "Net-(SEG4-b)") (class "Default")
      (node (ref "R46") (pin "1") (pinfunction "1_1") (pintype "passive"))
      (node (ref "SEG4") (pin "6") (pinfunction "b_6") (pintype "passive"))
    )
    (net (code "74") (name "Net-(SEG4-c)") (class "Default")
      (node (ref "R45") (pin "1") (pinfunction "1_1") (pintype "passive"))
      (node (ref "SEG4") (pin "4") (pinfunction "c_4") (pintype "passive"))
    )
    (net (code "75") (name "Net-(SEG4-d)") (class "Default")
      (node (ref "R44") (pin "1") (pinfunction "1_1") (pintype "passive"))
      (node (ref "SEG4") (pin "2") (pinfunction "d_2") (pintype "passive"))
    )
    (net (code "76") (name "Net-(SEG4-e)") (class "Default")
      (node (ref "R43") (pin "1") (pinfunction "1_1") (pintype "passive"))
      (node (ref "SEG4") (pin "1") (pinfunction "e_1") (pintype "passive"))
    )
    (net (code "77") (name "Net-(SEG4-f)") (class "Default")
      (node (ref "R38") (pin "1") (pinfunction "1_1") (pintype "passive"))
      (node (ref "SEG4") (pin "9") (pinfunction "f_9") (pintype "passive"))
    )
    (net (code "78") (name "Net-(SEG4-g)") (class "Default")
      (node (ref "R37") (pin "1") (pinfunction "1_1") (pintype "passive"))
      (node (ref "SEG4") (pin "10") (pinfunction "g_10") (pintype "passive"))
    )
    (net (code "79") (name "Net-(U1-PA0{slash}~{RESET}{slash}UPDI)") (class "Default")
      (node (ref "R2") (pin "2") (pinfunction "2_2") (pintype "passive"))
      (node (ref "U1") (pin "19") (pinfunction "PA0/~{RESET}/UPDI_19") (pintype "bidirectional"))
    )
    (net (code "80") (name "Net-(U3-a)") (class "Default")
      (node (ref "R18") (pin "2") (pinfunction "2_2") (pintype "passive"))
      (node (ref "U3") (pin "13") (pinfunction "a_13") (pintype "output"))
    )
    (net (code "81") (name "Net-(U3-b)") (class "Default")
      (node (ref "R17") (pin "2") (pinfunction "2_2") (pintype "passive"))
      (node (ref "U3") (pin "12") (pinfunction "b_12") (pintype "output"))
    )
    (net (code "82") (name "Net-(U3-c)") (class "Default")
      (node (ref "R16") (pin "2") (pinfunction "2_2") (pintype "passive"))
      (node (ref "U3") (pin "11") (pinfunction "c_11") (pintype "output"))
    )
    (net (code "83") (name "Net-(U3-d)") (class "Default")
      (node (ref "R15") (pin "2") (pinfunction "2_2") (pintype "passive"))
      (node (ref "U3") (pin "10") (pinfunction "d_10") (pintype "output"))
    )
    (net (code "84") (name "Net-(U3-e)") (class "Default")
      (node (ref "R14") (pin "2") (pinfunction "2_2") (pintype "passive"))
      (node (ref "U3") (pin "9") (pinfunction "e_9") (pintype "output"))
    )
    (net (code "85") (name "Net-(U3-f)") (class "Default")
      (node (ref "R13") (pin "2") (pinfunction "2_2") (pintype "passive"))
      (node (ref "U3") (pin "15") (pinfunction "f_15") (pintype "output"))
    )
    (net (code "86") (name "Net-(U3-g)") (class "Default")
      (node (ref "R11") (pin "2") (pinfunction "2_2") (pintype "passive"))
      (node (ref "U3") (pin "14") (pinfunction "g_14") (pintype "output"))
    )
    (net (code "87") (name "Net-(U4-Q7S)") (class "Default")
      (node (ref "U4") (pin "9") (pinfunction "Q7S_9") (pintype "output"))
      (node (ref "U6") (pin "14") (pinfunction "DS_14") (pintype "input"))
    )
    (net (code "88") (name "Net-(U5-a)") (class "Default")
      (node (ref "R27") (pin "2") (pinfunction "2_2") (pintype "passive"))
      (node (ref "U5") (pin "13") (pinfunction "a_13") (pintype "output"))
    )
    (net (code "89") (name "Net-(U5-b)") (class "Default")
      (node (ref "R26") (pin "2") (pinfunction "2_2") (pintype "passive"))
      (node (ref "U5") (pin "12") (pinfunction "b_12") (pintype "output"))
    )
    (net (code "90") (name "Net-(U5-c)") (class "Default")
      (node (ref "R25") (pin "2") (pinfunction "2_2") (pintype "passive"))
      (node (ref "U5") (pin "11") (pinfunction "c_11") (pintype "output"))
    )
    (net (code "91") (name "Net-(U5-d)") (class "Default")
      (node (ref "R24") (pin "2") (pinfunction "2_2") (pintype "passive"))
      (node (ref "U5") (pin "10") (pinfunction "d_10") (pintype "output"))
    )
    (net (code "92") (name "Net-(U5-e)") (class "Default")
      (node (ref "R23") (pin "2") (pinfunction "2_2") (pintype "passive"))
      (node (ref "U5") (pin "9") (pinfunction "e_9") (pintype "output"))
    )
    (net (code "93") (name "Net-(U5-f)") (class "Default")
      (node (ref "R22") (pin "2") (pinfunction "2_2") (pintype "passive"))
      (node (ref "U5") (pin "15") (pinfunction "f_15") (pintype "output"))
    )
    (net (code "94") (name "Net-(U5-g)") (class "Default")
      (node (ref "R21") (pin "2") (pinfunction "2_2") (pintype "passive"))
      (node (ref "U5") (pin "14") (pinfunction "g_14") (pintype "output"))
    )
    (net (code "95") (name "Net-(U6-Q7S)") (class "Default")
      (node (ref "U6") (pin "9") (pinfunction "Q7S_9") (pintype "output"))
      (node (ref "U8") (pin "14") (pinfunction "DS_14") (pintype "input"))
    )
    (net (code "96") (name "Net-(U7-a)") (class "Default")
      (node (ref "R35") (pin "2") (pinfunction "2_2") (pintype "passive"))
      (node (ref "U7") (pin "13") (pinfunction "a_13") (pintype "output"))
    )
    (net (code "97") (name "Net-(U7-b)") (class "Default")
      (node (ref "R34") (pin "2") (pinfunction "2_2") (pintype "passive"))
      (node (ref "U7") (pin "12") (pinfunction "b_12") (pintype "output"))
    )
    (net (code "98") (name "Net-(U7-c)") (class "Default")
      (node (ref "R33") (pin "2") (pinfunction "2_2") (pintype "passive"))
      (node (ref "U7") (pin "11") (pinfunction "c_11") (pintype "output"))
    )
    (net (code "99") (name "Net-(U7-d)") (class "Default")
      (node (ref "R32") (pin "2") (pinfunction "2_2") (pintype "passive"))
      (node (ref "U7") (pin "10") (pinfunction "d_10") (pintype "output"))
    )
    (net (code "100") (name "Net-(U7-e)") (class "Default")
      (node (ref "R31") (pin "2") (pinfunction "2_2") (pintype "passive"))
      (node (ref "U7") (pin "9") (pinfunction "e_9") (pintype "output"))
    )
    (net (code "101") (name "Net-(U7-f)") (class "Default")
      (node (ref "R30") (pin "2") (pinfunction "2_2") (pintype "passive"))
      (node (ref "U7") (pin "15") (pinfunction "f_15") (pintype "output"))
    )
    (net (code "102") (name "Net-(U7-g)") (class "Default")
      (node (ref "R29") (pin "2") (pinfunction "2_2") (pintype "passive"))
      (node (ref "U7") (pin "14") (pinfunction "g_14") (pintype "output"))
    )
    (net (code "103") (name "Net-(U9-a)") (class "Default")
      (node (ref "R47") (pin "2") (pinfunction "2_2") (pintype "passive"))
      (node (ref "U9") (pin "13") (pinfunction "a_13") (pintype "output"))
    )
    (net (code "104") (name "Net-(U9-b)") (class "Default")
      (node (ref "R46") (pin "2") (pinfunction "2_2") (pintype "passive"))
      (node (ref "U9") (pin "12") (pinfunction "b_12") (pintype "output"))
    )
    (net (code "105") (name "Net-(U9-c)") (class "Default")
      (node (ref "R45") (pin "2") (pinfunction "2_2") (pintype "passive"))
      (node (ref "U9") (pin "11") (pinfunction "c_11") (pintype "output"))
    )
    (net (code "106") (name "Net-(U9-d)") (class "Default")
      (node (ref "R44") (pin "2") (pinfunction "2_2") (pintype "passive"))
      (node (ref "U9") (pin "10") (pinfunction "d_10") (pintype "output"))
    )
    (net (code "107") (name "Net-(U9-e)") (class "Default")
      (node (ref "R43") (pin "2") (pinfunction "2_2") (pintype "passive"))
      (node (ref "U9") (pin "9") (pinfunction "e_9") (pintype "output"))
    )
    (net (code "108") (name "Net-(U9-f)") (class "Default")
      (node (ref "R38") (pin "2") (pinfunction "2_2") (pintype "passive"))
      (node (ref "U9") (pin "15") (pinfunction "f_15") (pintype "output"))
    )
    (net (code "109") (name "Net-(U9-g)") (class "Default")
      (node (ref "R37") (pin "2") (pinfunction "2_2") (pintype "passive"))
      (node (ref "U9") (pin "14") (pinfunction "g_14") (pintype "output"))
    )
    (net (code "110") (name "unconnected-(J7-Dn1-PadA7)") (class "Default")
      (node (ref "J7") (pin "A7") (pinfunction "Dn1_A7") (pintype "bidirectional+no_connect"))
    )
    (net (code "111") (name "unconnected-(J7-Dn2-PadB7)") (class "Default")
      (node (ref "J7") (pin "B7") (pinfunction "Dn2_B7") (pintype "bidirectional+no_connect"))
    )
    (net (code "112") (name "unconnected-(J7-Dp1-PadA6)") (class "Default")
      (node (ref "J7") (pin "A6") (pinfunction "Dp1_A6") (pintype "bidirectional+no_connect"))
    )
    (net (code "113") (name "unconnected-(J7-Dp2-PadB6)") (class "Default")
      (node (ref "J7") (pin "B6") (pinfunction "Dp2_B6") (pintype "bidirectional+no_connect"))
    )
    (net (code "114") (name "unconnected-(J7-SBU1-PadA8)") (class "Default")
      (node (ref "J7") (pin "A8") (pinfunction "SBU1_A8") (pintype "bidirectional+no_connect"))
    )
    (net (code "115") (name "unconnected-(J7-SBU2-PadB8)") (class "Default")
      (node (ref "J7") (pin "B8") (pinfunction "SBU2_B8") (pintype "power_in+no_connect"))
    )
    (net (code "116") (name "unconnected-(S1-Pad2)") (class "Default")
      (node (ref "S1") (pin "2") (pinfunction "2_2") (pintype "passive+no_connect"))
    )
    (net (code "117") (name "unconnected-(S1-Pad3)") (class "Default")
      (node (ref "S1") (pin "3") (pinfunction "3_3") (pintype "passive"))
    )
    (net (code "118") (name "unconnected-(S2-Pad2)") (class "Default")
      (node (ref "S2") (pin "2") (pinfunction "2_2") (pintype "passive+no_connect"))
    )
    (net (code "119") (name "unconnected-(S2-Pad3)") (class "Default")
      (node (ref "S2") (pin "3") (pinfunction "3_3") (pintype "passive"))
    )
    (net (code "120") (name "unconnected-(U1-PA7-Pad8)") (class "Default")
      (node (ref "U1") (pin "8") (pinfunction "PA7_8") (pintype "bidirectional"))
    )
    (net (code "121") (name "unconnected-(U1-PC3-Pad18)") (class "Default")
      (node (ref "U1") (pin "18") (pinfunction "PC3_18") (pintype "bidirectional"))
    )
    (net (code "122") (name "unconnected-(U2-CLKOUT-Pad1)") (class "Default")
      (node (ref "U2") (pin "1") (pinfunction "CLKOUT_1") (pintype "output+no_connect"))
    )
    (net (code "123") (name "unconnected-(U2-~{INT}-Pad2)") (class "Default")
      (node (ref "U2") (pin "2") (pinfunction "~{INT}_2") (pintype "input+no_connect"))
    )
    (net (code "124") (name "unconnected-(U8-Q4-Pad4)") (class "Default")
      (node (ref "U8") (pin "4") (pinfunction "Q4_4") (pintype "output"))
    )
    (net (code "125") (name "unconnected-(U8-Q5-Pad5)") (class "Default")
      (node (ref "U8") (pin "5") (pinfunction "Q5_5") (pintype "output"))
    )
    (net (code "126") (name "unconnected-(U8-Q6-Pad6)") (class "Default")
      (node (ref "U8") (pin "6") (pinfunction "Q6_6") (pintype "output"))
    )
    (net (code "127") (name "unconnected-(U8-Q7-Pad7)") (class "Default")
      (node (ref "U8") (pin "7") (pinfunction "Q7_7") (pintype "output"))
    )
    (net (code "128") (name "unconnected-(U8-Q7S-Pad9)") (class "Default")
      (node (ref "U8") (pin "9") (pinfunction "Q7S_9") (pintype "output"))
    )
  )
)
